# xc6xl9.net
KiCad netlist of a schematic drawn in EAGLE
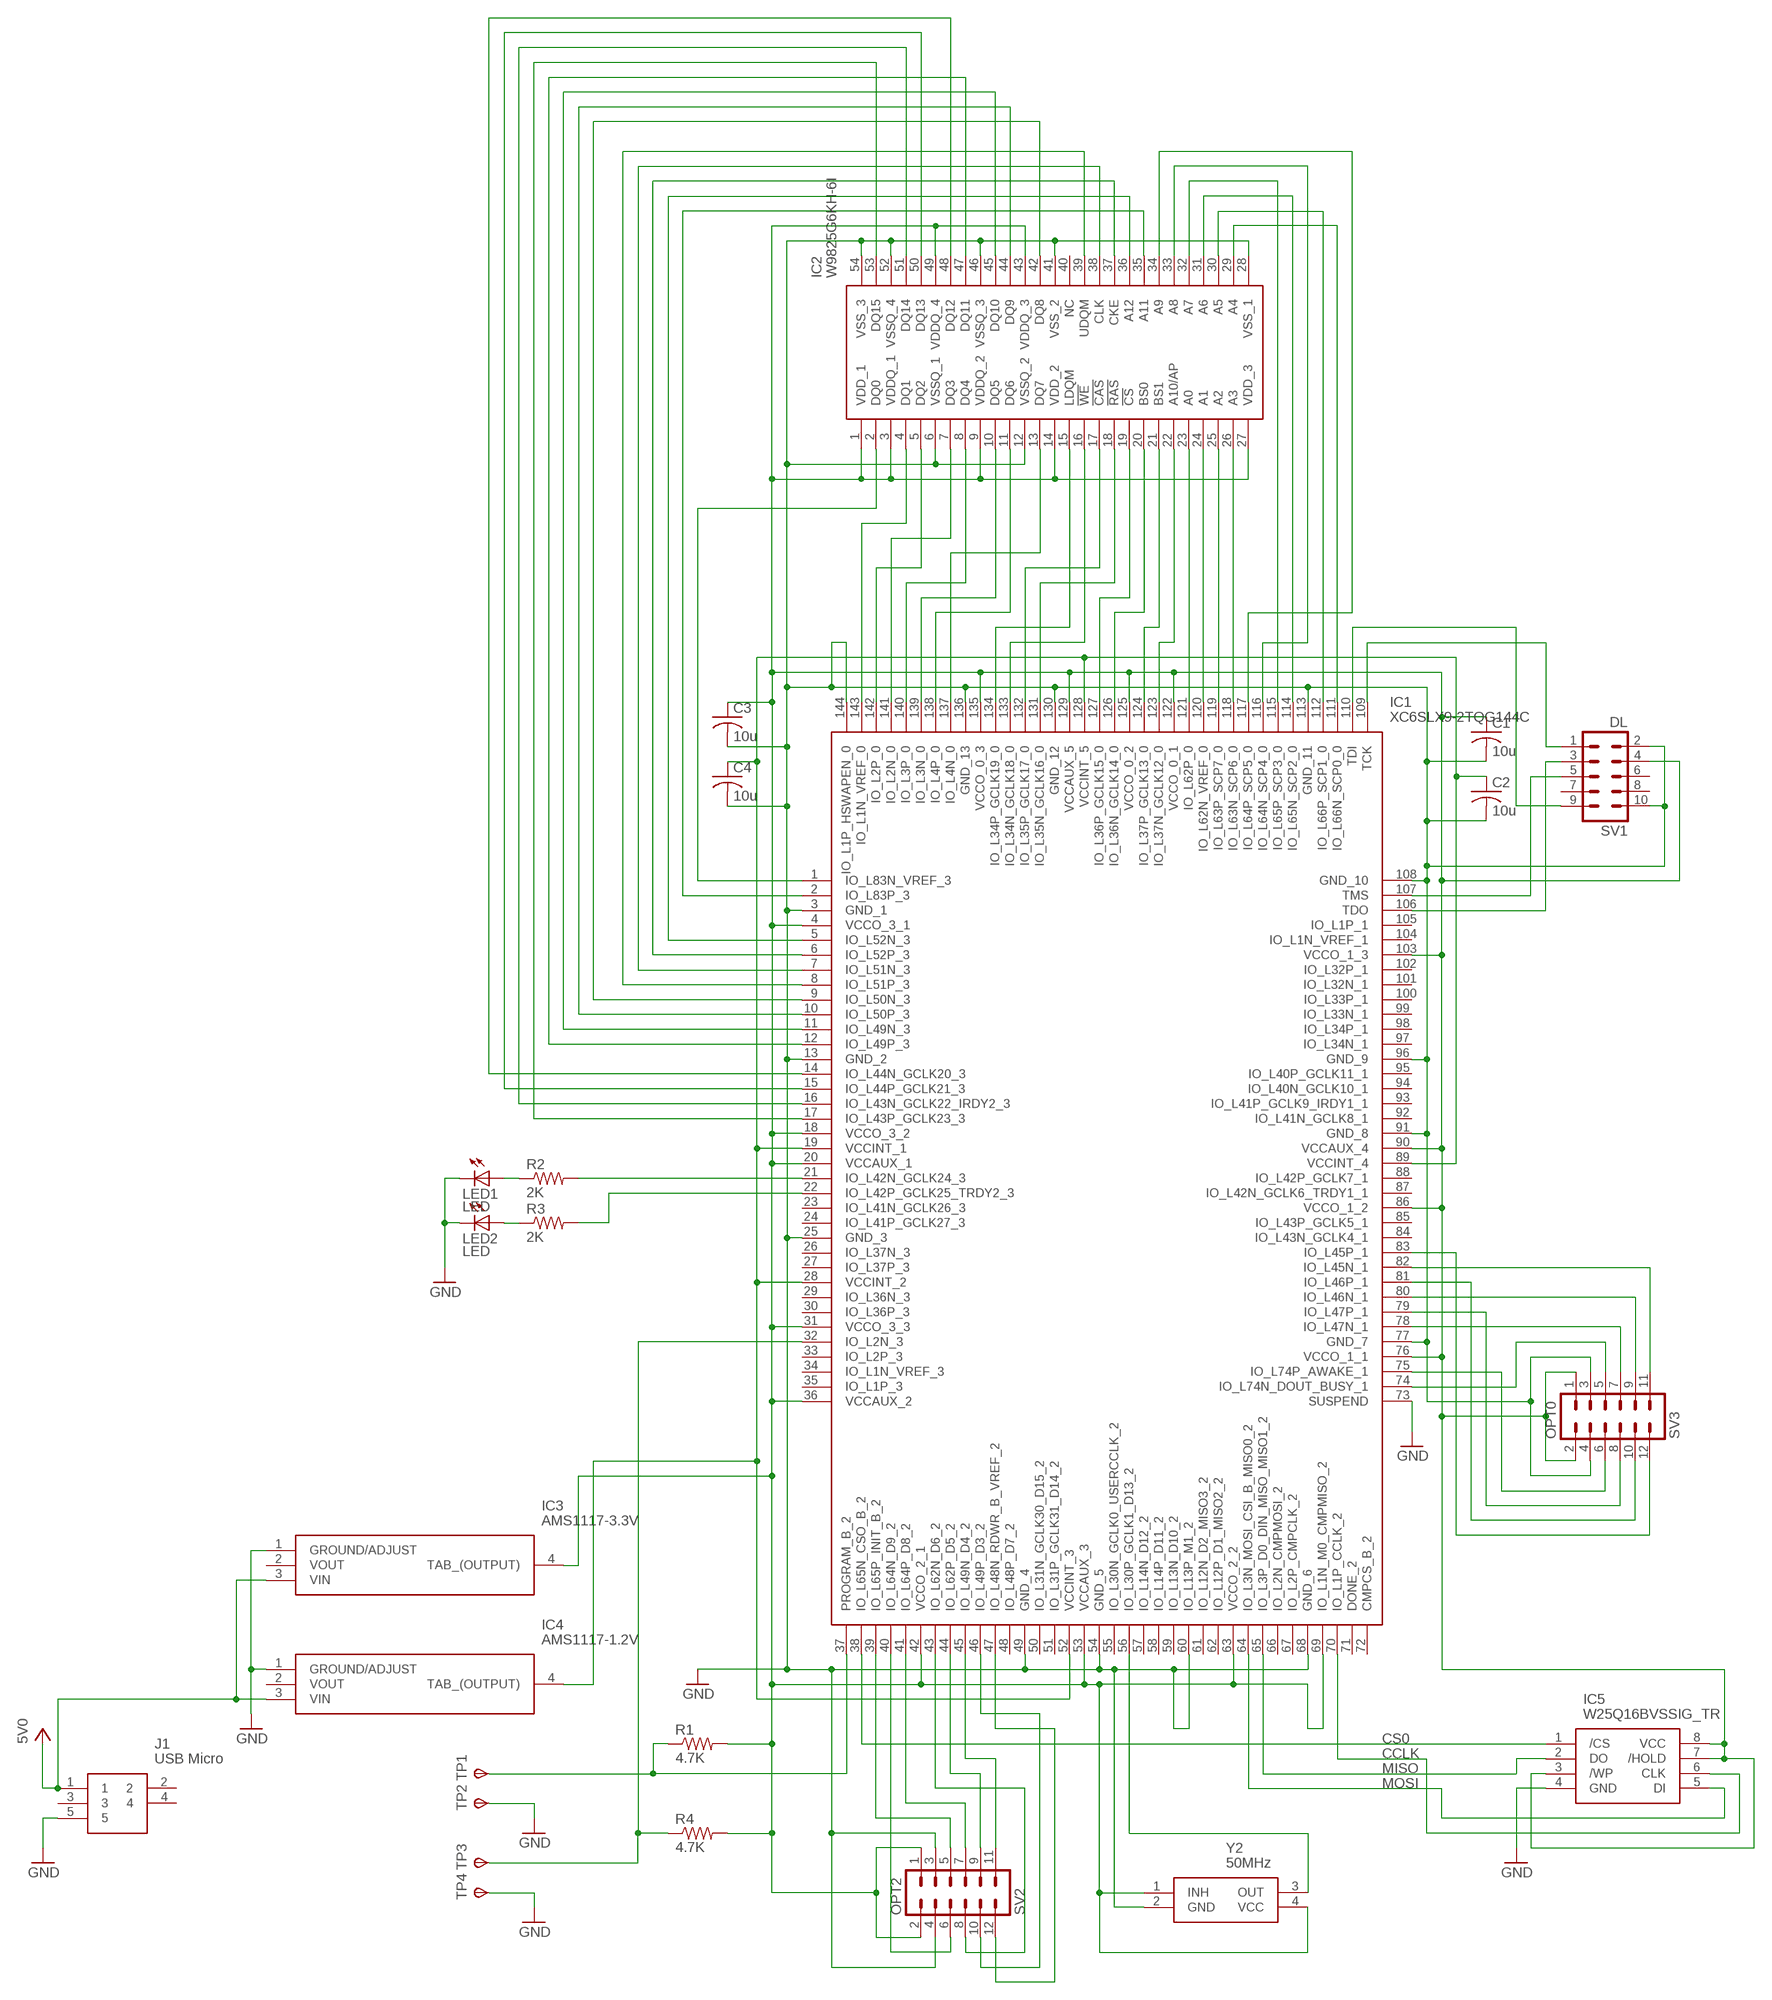
[diagram p0: schematic, sheet 1]

(export (version "E")
  (design (tool "Eeschema 10.0.6"))
  (components
    (comp (ref "C1")
      (value "10u")
      (footprint "eagle-import:C0805K")
      (libsource (lib "eagle-import") (part "C-USC0805K"))
    )
    (comp (ref "C2")
      (value "10u")
      (footprint "eagle-import:C0805K")
      (libsource (lib "eagle-import") (part "C-USC0805K"))
    )
    (comp (ref "C3")
      (value "10u")
      (footprint "eagle-import:C0805K")
      (libsource (lib "eagle-import") (part "C-USC0805K"))
    )
    (comp (ref "C4")
      (value "10u")
      (footprint "eagle-import:C0805K")
      (libsource (lib "eagle-import") (part "C-USC0805K"))
    )
    (comp (ref "IC1")
      (value "XC6SLX9-2TQG144C")
      (footprint "eagle-import:QFP50P2200X2200X160-144N")
      (fields (field (name "MOUSER_PART_NUMBER") "1732079"))
      (libsource (lib "eagle-import") (part "XC6SLX9-2TQG144C"))
    )
    (comp (ref "IC2")
      (value "W9825G6KH-6I")
      (footprint "eagle-import:SOP80P1176X120-54N")
      (fields
        (field (name "MOUSER_PART_NUMBER") "454-W9825G6KH-6I")
        (field (name "RS_PART_NUMBER") "1882632")
      )
      (libsource (lib "eagle-import") (part "W9825G6KH-6I"))
    )
    (comp (ref "IC3")
      (value "AMS1117-3.3V")
      (footprint "eagle-import:SOT229P700X180-4N")
      (fields (field (name "MANUFACTURER_PART_NUMBER") "ams1117-3.3v"))
      (libsource (lib "eagle-import") (part "AMS1117-3.3V"))
    )
    (comp (ref "IC4")
      (value "AMS1117-1.2V")
      (footprint "eagle-import:SOT229P700X180-4N")
      (fields (field (name "MANUFACTURER_PART_NUMBER") "ams1117-3.3v"))
      (libsource (lib "eagle-import") (part "AMS1117-3.3V"))
    )
    (comp (ref "IC5")
      (value "W25Q16BVSSIG_TR")
      (footprint "eagle-import:SOIC127P790X216-8N")
      (fields (field (name "ARROW_PART_NUMBER") "W25Q16BVSSIG TR"))
      (libsource (lib "eagle-import") (part "W25Q16BVSSIG_TR"))
    )
    (comp (ref "J1")
      (value "USB Micro")
      (footprint "eagle-import:10104110-0001LF")
      (fields (field (name "ARROW_PART_NUMBER") "10104110-0001LF") (field (name "RS_PART_NUMBER") "1738645"))
      (libsource (lib "eagle-import") (part "10104110-0001LF"))
    )
    (comp (ref "LED1")
      (value "LED")
      (footprint "eagle-import:CHIPLED_0805")
      (libsource (lib "eagle-import") (part "LEDCHIPLED_0805"))
    )
    (comp (ref "LED2")
      (value "LED")
      (footprint "eagle-import:CHIPLED_0805")
      (libsource (lib "eagle-import") (part "LEDCHIPLED_0805"))
    )
    (comp (ref "R1")
      (value "4.7K")
      (footprint "eagle-import:R0805")
      (libsource (lib "eagle-import") (part "R-US_R0805"))
    )
    (comp (ref "R2")
      (value "2K")
      (footprint "eagle-import:R0805")
      (libsource (lib "eagle-import") (part "R-US_R0805"))
    )
    (comp (ref "R3")
      (value "2K")
      (footprint "eagle-import:R0805")
      (libsource (lib "eagle-import") (part "R-US_R0805"))
    )
    (comp (ref "R4")
      (value "4.7K")
      (footprint "eagle-import:R0805")
      (libsource (lib "eagle-import") (part "R-US_R0805"))
    )
    (comp (ref "SV1")
      (value "DL")
      (footprint "eagle-import:MA05-2")
      (libsource (lib "eagle-import") (part "MA05-2"))
    )
    (comp (ref "SV2")
      (value "OPT2")
      (footprint "eagle-import:MA06-2")
      (libsource (lib "eagle-import") (part "MA06-2"))
    )
    (comp (ref "SV3")
      (value "OPT0")
      (footprint "eagle-import:MA06-2")
      (libsource (lib "eagle-import") (part "MA06-2"))
    )
    (comp (ref "TP1")
      (value "TPSTP10SQ")
      (footprint "eagle-import:TP10SQ")
      (libsource (lib "eagle-import") (part "TPSTP10SQ"))
    )
    (comp (ref "TP2")
      (value "TPSTP10SQ")
      (footprint "eagle-import:TP10SQ")
      (libsource (lib "eagle-import") (part "TPSTP10SQ"))
    )
    (comp (ref "TP3")
      (value "TPSTP10SQ")
      (footprint "eagle-import:TP10SQ")
      (libsource (lib "eagle-import") (part "TPSTP10SQ"))
    )
    (comp (ref "TP4")
      (value "TPSTP10SQ")
      (footprint "eagle-import:TP10SQ")
      (libsource (lib "eagle-import") (part "TPSTP10SQ"))
    )
    (comp (ref "Y2")
      (value "50MHz")
      (footprint "eagle-import:KC5032A12.0000CM0E00")
      (fields
        (field (name "MANUFACTURER_PART_NUMBER") "KC5032A80.0000C10E00")
        (field (name "MOUSER_PART_NUMBER") "1110767P")
      )
      (libsource (lib "eagle-import") (part "KC5032A80.0000C10E00"))
    )
  )
  (nets
    (net (code "1") (name "/CCLK") (class "Default")
      (node (ref "IC1") (pin "70") (pinfunction "IO_L1P_CCLK_2_70") (pintype "bidirectional"))
      (node (ref "IC5") (pin "6") (pinfunction "CLK_6") (pintype "bidirectional"))
    )
    (net (code "2") (name "/CS0") (class "Default")
      (node (ref "IC1") (pin "38") (pinfunction "IO_L65N_CSO_B_2_38") (pintype "bidirectional"))
      (node (ref "IC5") (pin "1") (pinfunction "/CS_1") (pintype "bidirectional"))
    )
    (net (code "3") (name "/MISO") (class "Default")
      (node (ref "IC1") (pin "65") (pinfunction "IO_L3P_D0_DIN_MISO_MISO1_2_65") (pintype "bidirectional"))
      (node (ref "IC5") (pin "2") (pinfunction "DO_2") (pintype "bidirectional"))
    )
    (net (code "4") (name "/MOSI") (class "Default")
      (node (ref "IC1") (pin "64") (pinfunction "IO_L3N_MOSI_CSI_B_MISO0_2_64") (pintype "bidirectional"))
      (node (ref "IC5") (pin "5") (pinfunction "DI_5") (pintype "bidirectional"))
    )
    (net (code "5") (name "5V0") (class "Default")
      (node (ref "IC3") (pin "3") (pinfunction "VIN_3") (pintype "bidirectional"))
      (node (ref "IC4") (pin "3") (pinfunction "VIN_3") (pintype "bidirectional"))
      (node (ref "J1") (pin "1") (pinfunction "1_1") (pintype "bidirectional"))
    )
    (net (code "6") (name "GND") (class "Default")
      (node (ref "C1") (pin "2") (pinfunction "2_2") (pintype "passive"))
      (node (ref "C2") (pin "2") (pinfunction "2_2") (pintype "passive"))
      (node (ref "C3") (pin "2") (pinfunction "2_2") (pintype "passive"))
      (node (ref "C4") (pin "2") (pinfunction "2_2") (pintype "passive"))
      (node (ref "IC1") (pin "108") (pinfunction "GND_10_108") (pintype "bidirectional"))
      (node (ref "IC1") (pin "113") (pinfunction "GND_11_113") (pintype "bidirectional"))
      (node (ref "IC1") (pin "13") (pinfunction "GND_2_13") (pintype "bidirectional"))
      (node (ref "IC1") (pin "130") (pinfunction "GND_12_130") (pintype "bidirectional"))
      (node (ref "IC1") (pin "136") (pinfunction "GND_13_136") (pintype "bidirectional"))
      (node (ref "IC1") (pin "144") (pinfunction "IO_L1P_HSWAPEN_0_144") (pintype "bidirectional"))
      (node (ref "IC1") (pin "25") (pinfunction "GND_3_25") (pintype "bidirectional"))
      (node (ref "IC1") (pin "3") (pinfunction "GND_1_3") (pintype "bidirectional"))
      (node (ref "IC1") (pin "49") (pinfunction "GND_4_49") (pintype "bidirectional"))
      (node (ref "IC1") (pin "54") (pinfunction "GND_5_54") (pintype "bidirectional"))
      (node (ref "IC1") (pin "60") (pinfunction "IO_L13P_M1_2_60") (pintype "bidirectional"))
      (node (ref "IC1") (pin "68") (pinfunction "GND_6_68") (pintype "bidirectional"))
      (node (ref "IC1") (pin "73") (pinfunction "SUSPEND_73") (pintype "bidirectional"))
      (node (ref "IC1") (pin "77") (pinfunction "GND_7_77") (pintype "bidirectional"))
      (node (ref "IC1") (pin "91") (pinfunction "GND_8_91") (pintype "bidirectional"))
      (node (ref "IC1") (pin "96") (pinfunction "GND_9_96") (pintype "bidirectional"))
      (node (ref "IC2") (pin "12") (pinfunction "VSSQ_2_12") (pintype "bidirectional"))
      (node (ref "IC2") (pin "28") (pinfunction "VSS_1_28") (pintype "bidirectional"))
      (node (ref "IC2") (pin "41") (pinfunction "VSS_2_41") (pintype "bidirectional"))
      (node (ref "IC2") (pin "46") (pinfunction "VSSQ_3_46") (pintype "bidirectional"))
      (node (ref "IC2") (pin "52") (pinfunction "VSSQ_4_52") (pintype "bidirectional"))
      (node (ref "IC2") (pin "54") (pinfunction "VSS_3_54") (pintype "bidirectional"))
      (node (ref "IC2") (pin "6") (pinfunction "VSSQ_1_6") (pintype "bidirectional"))
      (node (ref "IC3") (pin "1") (pinfunction "GROUND/ADJUST_1") (pintype "bidirectional"))
      (node (ref "IC4") (pin "1") (pinfunction "GROUND/ADJUST_1") (pintype "bidirectional"))
      (node (ref "IC5") (pin "4") (pinfunction "GND_4") (pintype "bidirectional"))
      (node (ref "J1") (pin "5") (pinfunction "5_5") (pintype "bidirectional"))
      (node (ref "LED1") (pin "C") (pinfunction "C_C") (pintype "passive"))
      (node (ref "LED2") (pin "C") (pinfunction "C_C") (pintype "passive"))
      (node (ref "SV1") (pin "10") (pinfunction "10_10") (pintype "passive"))
      (node (ref "SV1") (pin "2") (pinfunction "2_2") (pintype "passive"))
      (node (ref "SV2") (pin "3") (pinfunction "3_3") (pintype "passive"))
      (node (ref "SV2") (pin "4") (pinfunction "4_4") (pintype "passive"))
      (node (ref "SV3") (pin "3") (pinfunction "3_3") (pintype "passive"))
      (node (ref "SV3") (pin "4") (pinfunction "4_4") (pintype "passive"))
      (node (ref "TP2") (pin "TP") (pinfunction "PP_TP") (pintype "input"))
      (node (ref "TP4") (pin "TP") (pinfunction "PP_TP") (pintype "input"))
      (node (ref "Y2") (pin "2") (pinfunction "GND_2") (pintype "bidirectional"))
    )
    (net (code "7") (name "Net-(IC1-IO_L1N_M0_CMPMISO_2)") (class "Default")
      (node (ref "C1") (pin "1") (pinfunction "1_1") (pintype "passive"))
      (node (ref "C3") (pin "1") (pinfunction "1_1") (pintype "passive"))
      (node (ref "IC1") (pin "103") (pinfunction "VCCO_1_3_103") (pintype "bidirectional"))
      (node (ref "IC1") (pin "122") (pinfunction "VCCO_0_1_122") (pintype "bidirectional"))
      (node (ref "IC1") (pin "125") (pinfunction "VCCO_0_2_125") (pintype "bidirectional"))
      (node (ref "IC1") (pin "129") (pinfunction "VCCAUX_5_129") (pintype "bidirectional"))
      (node (ref "IC1") (pin "135") (pinfunction "VCCO_0_3_135") (pintype "bidirectional"))
      (node (ref "IC1") (pin "18") (pinfunction "VCCO_3_2_18") (pintype "bidirectional"))
      (node (ref "IC1") (pin "20") (pinfunction "VCCAUX_1_20") (pintype "bidirectional"))
      (node (ref "IC1") (pin "31") (pinfunction "VCCO_3_3_31") (pintype "bidirectional"))
      (node (ref "IC1") (pin "36") (pinfunction "VCCAUX_2_36") (pintype "bidirectional"))
      (node (ref "IC1") (pin "4") (pinfunction "VCCO_3_1_4") (pintype "bidirectional"))
      (node (ref "IC1") (pin "42") (pinfunction "VCCO_2_1_42") (pintype "bidirectional"))
      (node (ref "IC1") (pin "53") (pinfunction "VCCAUX_3_53") (pintype "bidirectional"))
      (node (ref "IC1") (pin "63") (pinfunction "VCCO_2_2_63") (pintype "bidirectional"))
      (node (ref "IC1") (pin "69") (pinfunction "IO_L1N_M0_CMPMISO_2_69") (pintype "bidirectional"))
      (node (ref "IC1") (pin "76") (pinfunction "VCCO_1_1_76") (pintype "bidirectional"))
      (node (ref "IC1") (pin "86") (pinfunction "VCCO_1_2_86") (pintype "bidirectional"))
      (node (ref "IC1") (pin "90") (pinfunction "VCCAUX_4_90") (pintype "bidirectional"))
      (node (ref "IC2") (pin "1") (pinfunction "VDD_1_1") (pintype "bidirectional"))
      (node (ref "IC2") (pin "14") (pinfunction "VDD_2_14") (pintype "bidirectional"))
      (node (ref "IC2") (pin "27") (pinfunction "VDD_3_27") (pintype "bidirectional"))
      (node (ref "IC2") (pin "3") (pinfunction "VDDQ_1_3") (pintype "bidirectional"))
      (node (ref "IC2") (pin "43") (pinfunction "VDDQ_3_43") (pintype "bidirectional"))
      (node (ref "IC2") (pin "49") (pinfunction "VDDQ_4_49") (pintype "bidirectional"))
      (node (ref "IC2") (pin "9") (pinfunction "VDDQ_2_9") (pintype "bidirectional"))
      (node (ref "IC3") (pin "4") (pinfunction "TAB_(OUTPUT)_4") (pintype "bidirectional"))
      (node (ref "IC5") (pin "3") (pinfunction "/WP_3") (pintype "bidirectional"))
      (node (ref "IC5") (pin "7") (pinfunction "/HOLD_7") (pintype "bidirectional"))
      (node (ref "IC5") (pin "8") (pinfunction "VCC_8") (pintype "bidirectional"))
      (node (ref "R1") (pin "2") (pinfunction "2_2") (pintype "passive"))
      (node (ref "R4") (pin "2") (pinfunction "2_2") (pintype "passive"))
      (node (ref "SV1") (pin "4") (pinfunction "4_4") (pintype "passive"))
      (node (ref "SV2") (pin "1") (pinfunction "1_1") (pintype "passive"))
      (node (ref "SV2") (pin "2") (pinfunction "2_2") (pintype "passive"))
      (node (ref "SV3") (pin "1") (pinfunction "1_1") (pintype "passive"))
      (node (ref "SV3") (pin "2") (pinfunction "2_2") (pintype "passive"))
      (node (ref "Y2") (pin "1") (pinfunction "INH_1") (pintype "bidirectional"))
      (node (ref "Y2") (pin "4") (pinfunction "VCC_4") (pintype "bidirectional"))
    )
    (net (code "8") (name "Net-(IC1-IO_L1N_VREF_0)") (class "Default")
      (node (ref "IC1") (pin "143") (pinfunction "IO_L1N_VREF_0_143") (pintype "bidirectional"))
      (node (ref "IC2") (pin "4") (pinfunction "DQ1_4") (pintype "bidirectional"))
    )
    (net (code "9") (name "Net-(IC1-IO_L2N_0)") (class "Default")
      (node (ref "IC1") (pin "141") (pinfunction "IO_L2N_0_141") (pintype "bidirectional"))
      (node (ref "IC2") (pin "7") (pinfunction "DQ3_7") (pintype "bidirectional"))
    )
    (net (code "10") (name "Net-(IC1-IO_L2N_3)") (class "Default")
      (node (ref "IC1") (pin "32") (pinfunction "IO_L2N_3_32") (pintype "bidirectional"))
      (node (ref "R4") (pin "1") (pinfunction "1_1") (pintype "passive"))
      (node (ref "TP3") (pin "TP") (pinfunction "PP_TP") (pintype "input"))
    )
    (net (code "11") (name "Net-(IC1-IO_L2P_0)") (class "Default")
      (node (ref "IC1") (pin "142") (pinfunction "IO_L2P_0_142") (pintype "bidirectional"))
      (node (ref "IC2") (pin "5") (pinfunction "DQ2_5") (pintype "bidirectional"))
    )
    (net (code "12") (name "Net-(IC1-IO_L3N_0)") (class "Default")
      (node (ref "IC1") (pin "139") (pinfunction "IO_L3N_0_139") (pintype "bidirectional"))
      (node (ref "IC2") (pin "10") (pinfunction "DQ5_10") (pintype "bidirectional"))
    )
    (net (code "13") (name "Net-(IC1-IO_L3P_0)") (class "Default")
      (node (ref "IC1") (pin "140") (pinfunction "IO_L3P_0_140") (pintype "bidirectional"))
      (node (ref "IC2") (pin "8") (pinfunction "DQ4_8") (pintype "bidirectional"))
    )
    (net (code "14") (name "Net-(IC1-IO_L4N_0)") (class "Default")
      (node (ref "IC1") (pin "137") (pinfunction "IO_L4N_0_137") (pintype "bidirectional"))
      (node (ref "IC2") (pin "13") (pinfunction "DQ7_13") (pintype "bidirectional"))
    )
    (net (code "15") (name "Net-(IC1-IO_L4P_0)") (class "Default")
      (node (ref "IC1") (pin "138") (pinfunction "IO_L4P_0_138") (pintype "bidirectional"))
      (node (ref "IC2") (pin "11") (pinfunction "DQ6_11") (pintype "bidirectional"))
    )
    (net (code "16") (name "Net-(IC1-IO_L30P_GCLK1_D13_2)") (class "Default")
      (node (ref "IC1") (pin "56") (pinfunction "IO_L30P_GCLK1_D13_2_56") (pintype "bidirectional"))
      (node (ref "Y2") (pin "3") (pinfunction "OUT_3") (pintype "bidirectional"))
    )
    (net (code "17") (name "Net-(IC1-IO_L34N_GCLK18_0)") (class "Default")
      (node (ref "IC1") (pin "133") (pinfunction "IO_L34N_GCLK18_0_133") (pintype "bidirectional"))
      (node (ref "IC2") (pin "16") (pinfunction "~{WE}_16") (pintype "bidirectional"))
    )
    (net (code "18") (name "Net-(IC1-IO_L34P_GCLK19_0)") (class "Default")
      (node (ref "IC1") (pin "134") (pinfunction "IO_L34P_GCLK19_0_134") (pintype "bidirectional"))
      (node (ref "IC2") (pin "15") (pinfunction "LDQM_15") (pintype "bidirectional"))
    )
    (net (code "19") (name "Net-(IC1-IO_L35N_GCLK16_0)") (class "Default")
      (node (ref "IC1") (pin "131") (pinfunction "IO_L35N_GCLK16_0_131") (pintype "bidirectional"))
      (node (ref "IC2") (pin "18") (pinfunction "~{RAS}_18") (pintype "bidirectional"))
    )
    (net (code "20") (name "Net-(IC1-IO_L35P_GCLK17_0)") (class "Default")
      (node (ref "IC1") (pin "132") (pinfunction "IO_L35P_GCLK17_0_132") (pintype "bidirectional"))
      (node (ref "IC2") (pin "17") (pinfunction "~{CAS}_17") (pintype "bidirectional"))
    )
    (net (code "21") (name "Net-(IC1-IO_L36N_GCLK14_0)") (class "Default")
      (node (ref "IC1") (pin "126") (pinfunction "IO_L36N_GCLK14_0_126") (pintype "bidirectional"))
      (node (ref "IC2") (pin "20") (pinfunction "BS0_20") (pintype "bidirectional"))
    )
    (net (code "22") (name "Net-(IC1-IO_L36P_GCLK15_0)") (class "Default")
      (node (ref "IC1") (pin "127") (pinfunction "IO_L36P_GCLK15_0_127") (pintype "bidirectional"))
      (node (ref "IC2") (pin "19") (pinfunction "~{CS}_19") (pintype "bidirectional"))
    )
    (net (code "23") (name "Net-(IC1-IO_L37N_GCLK12_0)") (class "Default")
      (node (ref "IC1") (pin "123") (pinfunction "IO_L37N_GCLK12_0_123") (pintype "bidirectional"))
      (node (ref "IC2") (pin "22") (pinfunction "A10/AP_22") (pintype "bidirectional"))
    )
    (net (code "24") (name "Net-(IC1-IO_L37P_GCLK13_0)") (class "Default")
      (node (ref "IC1") (pin "124") (pinfunction "IO_L37P_GCLK13_0_124") (pintype "bidirectional"))
      (node (ref "IC2") (pin "21") (pinfunction "BS1_21") (pintype "bidirectional"))
    )
    (net (code "25") (name "Net-(IC1-IO_L42N_GCLK24_3)") (class "Default")
      (node (ref "IC1") (pin "21") (pinfunction "IO_L42N_GCLK24_3_21") (pintype "bidirectional"))
      (node (ref "R2") (pin "2") (pinfunction "2_2") (pintype "passive"))
    )
    (net (code "26") (name "Net-(IC1-IO_L42P_GCLK25_TRDY2_3)") (class "Default")
      (node (ref "IC1") (pin "22") (pinfunction "IO_L42P_GCLK25_TRDY2_3_22") (pintype "bidirectional"))
      (node (ref "R3") (pin "2") (pinfunction "2_2") (pintype "passive"))
    )
    (net (code "27") (name "Net-(IC1-IO_L43N_GCLK22_IRDY2_3)") (class "Default")
      (node (ref "IC1") (pin "16") (pinfunction "IO_L43N_GCLK22_IRDY2_3_16") (pintype "bidirectional"))
      (node (ref "IC2") (pin "51") (pinfunction "DQ14_51") (pintype "bidirectional"))
    )
    (net (code "28") (name "Net-(IC1-IO_L43P_GCLK23_3)") (class "Default")
      (node (ref "IC1") (pin "17") (pinfunction "IO_L43P_GCLK23_3_17") (pintype "bidirectional"))
      (node (ref "IC2") (pin "53") (pinfunction "DQ15_53") (pintype "bidirectional"))
    )
    (net (code "29") (name "Net-(IC1-IO_L44N_GCLK20_3)") (class "Default")
      (node (ref "IC1") (pin "14") (pinfunction "IO_L44N_GCLK20_3_14") (pintype "bidirectional"))
      (node (ref "IC2") (pin "48") (pinfunction "DQ12_48") (pintype "bidirectional"))
    )
    (net (code "30") (name "Net-(IC1-IO_L44P_GCLK21_3)") (class "Default")
      (node (ref "IC1") (pin "15") (pinfunction "IO_L44P_GCLK21_3_15") (pintype "bidirectional"))
      (node (ref "IC2") (pin "50") (pinfunction "DQ13_50") (pintype "bidirectional"))
    )
    (net (code "31") (name "Net-(IC1-IO_L45N_1)") (class "Default")
      (node (ref "IC1") (pin "82") (pinfunction "IO_L45N_1_82") (pintype "bidirectional"))
      (node (ref "SV3") (pin "11") (pinfunction "11_11") (pintype "passive"))
    )
    (net (code "32") (name "Net-(IC1-IO_L45P_1)") (class "Default")
      (node (ref "IC1") (pin "83") (pinfunction "IO_L45P_1_83") (pintype "bidirectional"))
      (node (ref "SV3") (pin "12") (pinfunction "12_12") (pintype "passive"))
    )
    (net (code "33") (name "Net-(IC1-IO_L46N_1)") (class "Default")
      (node (ref "IC1") (pin "80") (pinfunction "IO_L46N_1_80") (pintype "bidirectional"))
      (node (ref "SV3") (pin "9") (pinfunction "9_9") (pintype "passive"))
    )
    (net (code "34") (name "Net-(IC1-IO_L46P_1)") (class "Default")
      (node (ref "IC1") (pin "81") (pinfunction "IO_L46P_1_81") (pintype "bidirectional"))
      (node (ref "SV3") (pin "10") (pinfunction "10_10") (pintype "passive"))
    )
    (net (code "35") (name "Net-(IC1-IO_L47N_1)") (class "Default")
      (node (ref "IC1") (pin "78") (pinfunction "IO_L47N_1_78") (pintype "bidirectional"))
      (node (ref "SV3") (pin "7") (pinfunction "7_7") (pintype "passive"))
    )
    (net (code "36") (name "Net-(IC1-IO_L47P_1)") (class "Default")
      (node (ref "IC1") (pin "79") (pinfunction "IO_L47P_1_79") (pintype "bidirectional"))
      (node (ref "SV3") (pin "8") (pinfunction "8_8") (pintype "passive"))
    )
    (net (code "37") (name "Net-(IC1-IO_L48N_RDWR_B_VREF_2)") (class "Default")
      (node (ref "IC1") (pin "47") (pinfunction "IO_L48N_RDWR_B_VREF_2_47") (pintype "bidirectional"))
      (node (ref "SV2") (pin "12") (pinfunction "12_12") (pintype "passive"))
    )
    (net (code "38") (name "Net-(IC1-IO_L49N_3)") (class "Default")
      (node (ref "IC1") (pin "11") (pinfunction "IO_L49N_3_11") (pintype "bidirectional"))
      (node (ref "IC2") (pin "45") (pinfunction "DQ10_45") (pintype "bidirectional"))
    )
    (net (code "39") (name "Net-(IC1-IO_L49N_D4_2)") (class "Default")
      (node (ref "IC1") (pin "45") (pinfunction "IO_L49N_D4_2_45") (pintype "bidirectional"))
      (node (ref "SV2") (pin "11") (pinfunction "11_11") (pintype "passive"))
    )
    (net (code "40") (name "Net-(IC1-IO_L49P_3)") (class "Default")
      (node (ref "IC1") (pin "12") (pinfunction "IO_L49P_3_12") (pintype "bidirectional"))
      (node (ref "IC2") (pin "47") (pinfunction "DQ11_47") (pintype "bidirectional"))
    )
    (net (code "41") (name "Net-(IC1-IO_L49P_D3_2)") (class "Default")
      (node (ref "IC1") (pin "46") (pinfunction "IO_L49P_D3_2_46") (pintype "bidirectional"))
      (node (ref "SV2") (pin "10") (pinfunction "10_10") (pintype "passive"))
    )
    (net (code "42") (name "Net-(IC1-IO_L50N_3)") (class "Default")
      (node (ref "IC1") (pin "9") (pinfunction "IO_L50N_3_9") (pintype "bidirectional"))
      (node (ref "IC2") (pin "42") (pinfunction "DQ8_42") (pintype "bidirectional"))
    )
    (net (code "43") (name "Net-(IC1-IO_L50P_3)") (class "Default")
      (node (ref "IC1") (pin "10") (pinfunction "IO_L50P_3_10") (pintype "bidirectional"))
      (node (ref "IC2") (pin "44") (pinfunction "DQ9_44") (pintype "bidirectional"))
    )
    (net (code "44") (name "Net-(IC1-IO_L51N_3)") (class "Default")
      (node (ref "IC1") (pin "7") (pinfunction "IO_L51N_3_7") (pintype "bidirectional"))
      (node (ref "IC2") (pin "38") (pinfunction "CLK_38") (pintype "bidirectional"))
    )
    (net (code "45") (name "Net-(IC1-IO_L51P_3)") (class "Default")
      (node (ref "IC1") (pin "8") (pinfunction "IO_L51P_3_8") (pintype "bidirectional"))
      (node (ref "IC2") (pin "39") (pinfunction "UDQM_39") (pintype "bidirectional"))
    )
    (net (code "46") (name "Net-(IC1-IO_L52N_3)") (class "Default")
      (node (ref "IC1") (pin "5") (pinfunction "IO_L52N_3_5") (pintype "bidirectional"))
      (node (ref "IC2") (pin "36") (pinfunction "A12_36") (pintype "bidirectional"))
    )
    (net (code "47") (name "Net-(IC1-IO_L52P_3)") (class "Default")
      (node (ref "IC1") (pin "6") (pinfunction "IO_L52P_3_6") (pintype "bidirectional"))
      (node (ref "IC2") (pin "37") (pinfunction "CKE_37") (pintype "bidirectional"))
    )
    (net (code "48") (name "Net-(IC1-IO_L62N_D6_2)") (class "Default")
      (node (ref "IC1") (pin "43") (pinfunction "IO_L62N_D6_2_43") (pintype "bidirectional"))
      (node (ref "SV2") (pin "8") (pinfunction "8_8") (pintype "passive"))
    )
    (net (code "49") (name "Net-(IC1-IO_L62N_VREF_0)") (class "Default")
      (node (ref "IC1") (pin "120") (pinfunction "IO_L62N_VREF_0_120") (pintype "bidirectional"))
      (node (ref "IC2") (pin "24") (pinfunction "A1_24") (pintype "bidirectional"))
    )
    (net (code "50") (name "Net-(IC1-IO_L62P_0)") (class "Default")
      (node (ref "IC1") (pin "121") (pinfunction "IO_L62P_0_121") (pintype "bidirectional"))
      (node (ref "IC2") (pin "23") (pinfunction "A0_23") (pintype "bidirectional"))
    )
    (net (code "51") (name "Net-(IC1-IO_L62P_D5_2)") (class "Default")
      (node (ref "IC1") (pin "44") (pinfunction "IO_L62P_D5_2_44") (pintype "bidirectional"))
      (node (ref "SV2") (pin "9") (pinfunction "9_9") (pintype "passive"))
    )
    (net (code "52") (name "Net-(IC1-IO_L63N_SCP6_0)") (class "Default")
      (node (ref "IC1") (pin "118") (pinfunction "IO_L63N_SCP6_0_118") (pintype "bidirectional"))
      (node (ref "IC2") (pin "26") (pinfunction "A3_26") (pintype "bidirectional"))
    )
    (net (code "53") (name "Net-(IC1-IO_L63P_SCP7_0)") (class "Default")
      (node (ref "IC1") (pin "119") (pinfunction "IO_L63P_SCP7_0_119") (pintype "bidirectional"))
      (node (ref "IC2") (pin "25") (pinfunction "A2_25") (pintype "bidirectional"))
    )
    (net (code "54") (name "Net-(IC1-IO_L64N_D9_2)") (class "Default")
      (node (ref "IC1") (pin "40") (pinfunction "IO_L64N_D9_2_40") (pintype "bidirectional"))
      (node (ref "SV2") (pin "6") (pinfunction "6_6") (pintype "passive"))
    )
    (net (code "55") (name "Net-(IC1-IO_L64N_SCP4_0)") (class "Default")
      (node (ref "IC1") (pin "116") (pinfunction "IO_L64N_SCP4_0_116") (pintype "bidirectional"))
      (node (ref "IC2") (pin "33") (pinfunction "A8_33") (pintype "bidirectional"))
    )
    (net (code "56") (name "Net-(IC1-IO_L64P_D8_2)") (class "Default")
      (node (ref "IC1") (pin "41") (pinfunction "IO_L64P_D8_2_41") (pintype "bidirectional"))
      (node (ref "SV2") (pin "7") (pinfunction "7_7") (pintype "passive"))
    )
    (net (code "57") (name "Net-(IC1-IO_L64P_SCP5_0)") (class "Default")
      (node (ref "IC1") (pin "117") (pinfunction "IO_L64P_SCP5_0_117") (pintype "bidirectional"))
      (node (ref "IC2") (pin "34") (pinfunction "A9_34") (pintype "bidirectional"))
    )
    (net (code "58") (name "Net-(IC1-IO_L65N_SCP2_0)") (class "Default")
      (node (ref "IC1") (pin "114") (pinfunction "IO_L65N_SCP2_0_114") (pintype "bidirectional"))
      (node (ref "IC2") (pin "31") (pinfunction "A6_31") (pintype "bidirectional"))
    )
    (net (code "59") (name "Net-(IC1-IO_L65P_INIT_B_2)") (class "Default")
      (node (ref "IC1") (pin "39") (pinfunction "IO_L65P_INIT_B_2_39") (pintype "bidirectional"))
      (node (ref "SV2") (pin "5") (pinfunction "5_5") (pintype "passive"))
    )
    (net (code "60") (name "Net-(IC1-IO_L65P_SCP3_0)") (class "Default")
      (node (ref "IC1") (pin "115") (pinfunction "IO_L65P_SCP3_0_115") (pintype "bidirectional"))
      (node (ref "IC2") (pin "32") (pinfunction "A7_32") (pintype "bidirectional"))
    )
    (net (code "61") (name "Net-(IC1-IO_L66N_SCP0_0)") (class "Default")
      (node (ref "IC1") (pin "111") (pinfunction "IO_L66N_SCP0_0_111") (pintype "bidirectional"))
      (node (ref "IC2") (pin "29") (pinfunction "A4_29") (pintype "bidirectional"))
    )
    (net (code "62") (name "Net-(IC1-IO_L66P_SCP1_0)") (class "Default")
      (node (ref "IC1") (pin "112") (pinfunction "IO_L66P_SCP1_0_112") (pintype "bidirectional"))
      (node (ref "IC2") (pin "30") (pinfunction "A5_30") (pintype "bidirectional"))
    )
    (net (code "63") (name "Net-(IC1-IO_L74N_DOUT_BUSY_1)") (class "Default")
      (node (ref "IC1") (pin "74") (pinfunction "IO_L74N_DOUT_BUSY_1_74") (pintype "bidirectional"))
      (node (ref "SV3") (pin "5") (pinfunction "5_5") (pintype "passive"))
    )
    (net (code "64") (name "Net-(IC1-IO_L74P_AWAKE_1)") (class "Default")
      (node (ref "IC1") (pin "75") (pinfunction "IO_L74P_AWAKE_1_75") (pintype "bidirectional"))
      (node (ref "SV3") (pin "6") (pinfunction "6_6") (pintype "passive"))
    )
    (net (code "65") (name "Net-(IC1-IO_L83N_VREF_3)") (class "Default")
      (node (ref "IC1") (pin "1") (pinfunction "IO_L83N_VREF_3_1") (pintype "bidirectional"))
      (node (ref "IC2") (pin "2") (pinfunction "DQ0_2") (pintype "bidirectional"))
    )
    (net (code "66") (name "Net-(IC1-IO_L83P_3)") (class "Default")
      (node (ref "IC1") (pin "2") (pinfunction "IO_L83P_3_2") (pintype "bidirectional"))
      (node (ref "IC2") (pin "35") (pinfunction "A11_35") (pintype "bidirectional"))
    )
    (net (code "67") (name "Net-(IC1-PROGRAM_B_2)") (class "Default")
      (node (ref "IC1") (pin "37") (pinfunction "PROGRAM_B_2_37") (pintype "bidirectional"))
      (node (ref "R1") (pin "1") (pinfunction "1_1") (pintype "passive"))
      (node (ref "TP1") (pin "TP") (pinfunction "PP_TP") (pintype "input"))
    )
    (net (code "68") (name "Net-(IC1-TCK)") (class "Default")
      (node (ref "IC1") (pin "109") (pinfunction "TCK_109") (pintype "bidirectional"))
      (node (ref "SV1") (pin "1") (pinfunction "1_1") (pintype "passive"))
    )
    (net (code "69") (name "Net-(IC1-TDI)") (class "Default")
      (node (ref "IC1") (pin "110") (pinfunction "TDI_110") (pintype "bidirectional"))
      (node (ref "SV1") (pin "9") (pinfunction "9_9") (pintype "passive"))
    )
    (net (code "70") (name "Net-(IC1-TDO)") (class "Default")
      (node (ref "IC1") (pin "106") (pinfunction "TDO_106") (pintype "bidirectional"))
      (node (ref "SV1") (pin "3") (pinfunction "3_3") (pintype "passive"))
    )
    (net (code "71") (name "Net-(IC1-TMS)") (class "Default")
      (node (ref "IC1") (pin "107") (pinfunction "TMS_107") (pintype "bidirectional"))
      (node (ref "SV1") (pin "5") (pinfunction "5_5") (pintype "passive"))
    )
    (net (code "72") (name "Net-(IC1-VCCINT_1)") (class "Default")
      (node (ref "C2") (pin "1") (pinfunction "1_1") (pintype "passive"))
      (node (ref "C4") (pin "1") (pinfunction "1_1") (pintype "passive"))
      (node (ref "IC1") (pin "128") (pinfunction "VCCINT_5_128") (pintype "bidirectional"))
      (node (ref "IC1") (pin "19") (pinfunction "VCCINT_1_19") (pintype "bidirectional"))
      (node (ref "IC1") (pin "28") (pinfunction "VCCINT_2_28") (pintype "bidirectional"))
      (node (ref "IC1") (pin "52") (pinfunction "VCCINT_3_52") (pintype "bidirectional"))
      (node (ref "IC1") (pin "89") (pinfunction "VCCINT_4_89") (pintype "bidirectional"))
      (node (ref "IC4") (pin "4") (pinfunction "TAB_(OUTPUT)_4") (pintype "bidirectional"))
    )
    (net (code "73") (name "Net-(LED1-PadA)") (class "Default")
      (node (ref "LED1") (pin "A") (pinfunction "A_A") (pintype "passive"))
      (node (ref "R2") (pin "1") (pinfunction "1_1") (pintype "passive"))
    )
    (net (code "74") (name "Net-(LED2-PadA)") (class "Default")
      (node (ref "LED2") (pin "A") (pinfunction "A_A") (pintype "passive"))
      (node (ref "R3") (pin "1") (pinfunction "1_1") (pintype "passive"))
    )
    (net (code "75") (name "unconnected-(IC1-CMPCS_B_2-Pad72)") (class "Default")
      (node (ref "IC1") (pin "72") (pinfunction "CMPCS_B_2_72") (pintype "bidirectional"))
    )
    (net (code "76") (name "unconnected-(IC1-DONE_2-Pad71)") (class "Default")
      (node (ref "IC1") (pin "71") (pinfunction "DONE_2_71") (pintype "bidirectional"))
    )
    (net (code "77") (name "unconnected-(IC1-IO_L1N_VREF_1-Pad104)") (class "Default")
      (node (ref "IC1") (pin "104") (pinfunction "IO_L1N_VREF_1_104") (pintype "bidirectional"))
    )
    (net (code "78") (name "unconnected-(IC1-IO_L1N_VREF_3-Pad34)") (class "Default")
      (node (ref "IC1") (pin "34") (pinfunction "IO_L1N_VREF_3_34") (pintype "bidirectional"))
    )
    (net (code "79") (name "unconnected-(IC1-IO_L1P_1-Pad105)") (class "Default")
      (node (ref "IC1") (pin "105") (pinfunction "IO_L1P_1_105") (pintype "bidirectional"))
    )
    (net (code "80") (name "unconnected-(IC1-IO_L1P_3-Pad35)") (class "Default")
      (node (ref "IC1") (pin "35") (pinfunction "IO_L1P_3_35") (pintype "bidirectional"))
    )
    (net (code "81") (name "unconnected-(IC1-IO_L2N_CMPMOSI_2-Pad66)") (class "Default")
      (node (ref "IC1") (pin "66") (pinfunction "IO_L2N_CMPMOSI_2_66") (pintype "bidirectional"))
    )
    (net (code "82") (name "unconnected-(IC1-IO_L2P_3-Pad33)") (class "Default")
      (node (ref "IC1") (pin "33") (pinfunction "IO_L2P_3_33") (pintype "bidirectional"))
    )
    (net (code "83") (name "unconnected-(IC1-IO_L2P_CMPCLK_2-Pad67)") (class "Default")
      (node (ref "IC1") (pin "67") (pinfunction "IO_L2P_CMPCLK_2_67") (pintype "bidirectional"))
    )
    (net (code "84") (name "unconnected-(IC1-IO_L12N_D2_MISO3_2-Pad61)") (class "Default")
      (node (ref "IC1") (pin "61") (pinfunction "IO_L12N_D2_MISO3_2_61") (pintype "bidirectional"))
    )
    (net (code "85") (name "unconnected-(IC1-IO_L12P_D1_MISO2_2-Pad62)") (class "Default")
      (node (ref "IC1") (pin "62") (pinfunction "IO_L12P_D1_MISO2_2_62") (pintype "bidirectional"))
    )
    (net (code "86") (name "unconnected-(IC1-IO_L13N_D10_2-Pad59)") (class "Default")
      (node (ref "IC1") (pin "59") (pinfunction "IO_L13N_D10_2_59") (pintype "bidirectional"))
    )
    (net (code "87") (name "unconnected-(IC1-IO_L14N_D12_2-Pad57)") (class "Default")
      (node (ref "IC1") (pin "57") (pinfunction "IO_L14N_D12_2_57") (pintype "bidirectional"))
    )
    (net (code "88") (name "unconnected-(IC1-IO_L14P_D11_2-Pad58)") (class "Default")
      (node (ref "IC1") (pin "58") (pinfunction "IO_L14P_D11_2_58") (pintype "bidirectional"))
    )
    (net (code "89") (name "unconnected-(IC1-IO_L30N_GCLK0_USERCCLK_2-Pad55)") (class "Default")
      (node (ref "IC1") (pin "55") (pinfunction "IO_L30N_GCLK0_USERCCLK_2_55") (pintype "bidirectional"))
    )
    (net (code "90") (name "unconnected-(IC1-IO_L31N_GCLK30_D15_2-Pad50)") (class "Default")
      (node (ref "IC1") (pin "50") (pinfunction "IO_L31N_GCLK30_D15_2_50") (pintype "bidirectional"))
    )
    (net (code "91") (name "unconnected-(IC1-IO_L31P_GCLK31_D14_2-Pad51)") (class "Default")
      (node (ref "IC1") (pin "51") (pinfunction "IO_L31P_GCLK31_D14_2_51") (pintype "bidirectional"))
    )
    (net (code "92") (name "unconnected-(IC1-IO_L32N_1-Pad101)") (class "Default")
      (node (ref "IC1") (pin "101") (pinfunction "IO_L32N_1_101") (pintype "bidirectional"))
    )
    (net (code "93") (name "unconnected-(IC1-IO_L32P_1-Pad102)") (class "Default")
      (node (ref "IC1") (pin "102") (pinfunction "IO_L32P_1_102") (pintype "bidirectional"))
    )
    (net (code "94") (name "unconnected-(IC1-IO_L33N_1-Pad99)") (class "Default")
      (node (ref "IC1") (pin "99") (pinfunction "IO_L33N_1_99") (pintype "bidirectional"))
    )
    (net (code "95") (name "unconnected-(IC1-IO_L33P_1-Pad100)") (class "Default")
      (node (ref "IC1") (pin "100") (pinfunction "IO_L33P_1_100") (pintype "bidirectional"))
    )
    (net (code "96") (name "unconnected-(IC1-IO_L34N_1-Pad97)") (class "Default")
      (node (ref "IC1") (pin "97") (pinfunction "IO_L34N_1_97") (pintype "bidirectional"))
    )
    (net (code "97") (name "unconnected-(IC1-IO_L34P_1-Pad98)") (class "Default")
      (node (ref "IC1") (pin "98") (pinfunction "IO_L34P_1_98") (pintype "bidirectional"))
    )
    (net (code "98") (name "unconnected-(IC1-IO_L36N_3-Pad29)") (class "Default")
      (node (ref "IC1") (pin "29") (pinfunction "IO_L36N_3_29") (pintype "bidirectional"))
    )
    (net (code "99") (name "unconnected-(IC1-IO_L36P_3-Pad30)") (class "Default")
      (node (ref "IC1") (pin "30") (pinfunction "IO_L36P_3_30") (pintype "bidirectional"))
    )
    (net (code "100") (name "unconnected-(IC1-IO_L37N_3-Pad26)") (class "Default")
      (node (ref "IC1") (pin "26") (pinfunction "IO_L37N_3_26") (pintype "bidirectional"))
    )
    (net (code "101") (name "unconnected-(IC1-IO_L37P_3-Pad27)") (class "Default")
      (node (ref "IC1") (pin "27") (pinfunction "IO_L37P_3_27") (pintype "bidirectional"))
    )
    (net (code "102") (name "unconnected-(IC1-IO_L40N_GCLK10_1-Pad94)") (class "Default")
      (node (ref "IC1") (pin "94") (pinfunction "IO_L40N_GCLK10_1_94") (pintype "bidirectional"))
    )
    (net (code "103") (name "unconnected-(IC1-IO_L40P_GCLK11_1-Pad95)") (class "Default")
      (node (ref "IC1") (pin "95") (pinfunction "IO_L40P_GCLK11_1_95") (pintype "bidirectional"))
    )
    (net (code "104") (name "unconnected-(IC1-IO_L41N_GCLK8_1-Pad92)") (class "Default")
      (node (ref "IC1") (pin "92") (pinfunction "IO_L41N_GCLK8_1_92") (pintype "bidirectional"))
    )
    (net (code "105") (name "unconnected-(IC1-IO_L41N_GCLK26_3-Pad23)") (class "Default")
      (node (ref "IC1") (pin "23") (pinfunction "IO_L41N_GCLK26_3_23") (pintype "bidirectional"))
    )
    (net (code "106") (name "unconnected-(IC1-IO_L41P_GCLK9_IRDY1_1-Pad93)") (class "Default")
      (node (ref "IC1") (pin "93") (pinfunction "IO_L41P_GCLK9_IRDY1_1_93") (pintype "bidirectional"))
    )
    (net (code "107") (name "unconnected-(IC1-IO_L41P_GCLK27_3-Pad24)") (class "Default")
      (node (ref "IC1") (pin "24") (pinfunction "IO_L41P_GCLK27_3_24") (pintype "bidirectional"))
    )
    (net (code "108") (name "unconnected-(IC1-IO_L42N_GCLK6_TRDY1_1-Pad87)") (class "Default")
      (node (ref "IC1") (pin "87") (pinfunction "IO_L42N_GCLK6_TRDY1_1_87") (pintype "bidirectional"))
    )
    (net (code "109") (name "unconnected-(IC1-IO_L42P_GCLK7_1-Pad88)") (class "Default")
      (node (ref "IC1") (pin "88") (pinfunction "IO_L42P_GCLK7_1_88") (pintype "bidirectional"))
    )
    (net (code "110") (name "unconnected-(IC1-IO_L43N_GCLK4_1-Pad84)") (class "Default")
      (node (ref "IC1") (pin "84") (pinfunction "IO_L43N_GCLK4_1_84") (pintype "bidirectional"))
    )
    (net (code "111") (name "unconnected-(IC1-IO_L43P_GCLK5_1-Pad85)") (class "Default")
      (node (ref "IC1") (pin "85") (pinfunction "IO_L43P_GCLK5_1_85") (pintype "bidirectional"))
    )
    (net (code "112") (name "unconnected-(IC1-IO_L48P_D7_2-Pad48)") (class "Default")
      (node (ref "IC1") (pin "48") (pinfunction "IO_L48P_D7_2_48") (pintype "bidirectional"))
    )
    (net (code "113") (name "unconnected-(IC2-NC-Pad40)") (class "Default")
      (node (ref "IC2") (pin "40") (pinfunction "NC_40") (pintype "no_connect"))
    )
    (net (code "114") (name "unconnected-(IC3-VOUT-Pad2)") (class "Default")
      (node (ref "IC3") (pin "2") (pinfunction "VOUT_2") (pintype "bidirectional"))
    )
    (net (code "115") (name "unconnected-(IC4-VOUT-Pad2)") (class "Default")
      (node (ref "IC4") (pin "2") (pinfunction "VOUT_2") (pintype "bidirectional"))
    )
    (net (code "116") (name "unconnected-(J1-Pad2)") (class "Default")
      (node (ref "J1") (pin "2") (pinfunction "2_2") (pintype "bidirectional"))
    )
    (net (code "117") (name "unconnected-(J1-Pad3)") (class "Default")
      (node (ref "J1") (pin "3") (pinfunction "3_3") (pintype "bidirectional"))
    )
    (net (code "118") (name "unconnected-(J1-Pad4)") (class "Default")
      (node (ref "J1") (pin "4") (pinfunction "4_4") (pintype "bidirectional"))
    )
    (net (code "119") (name "unconnected-(SV1-Pad6)") (class "Default")
      (node (ref "SV1") (pin "6") (pinfunction "6_6") (pintype "passive"))
    )
    (net (code "120") (name "unconnected-(SV1-Pad7)") (class "Default")
      (node (ref "SV1") (pin "7") (pinfunction "7_7") (pintype "passive"))
    )
    (net (code "121") (name "unconnected-(SV1-Pad8)") (class "Default")
      (node (ref "SV1") (pin "8") (pinfunction "8_8") (pintype "passive"))
    )
  )
)
